# 03_PHOTOELECTRIC_SENSOR.net
KiCad netlist of a schematic drawn in Altium Designer
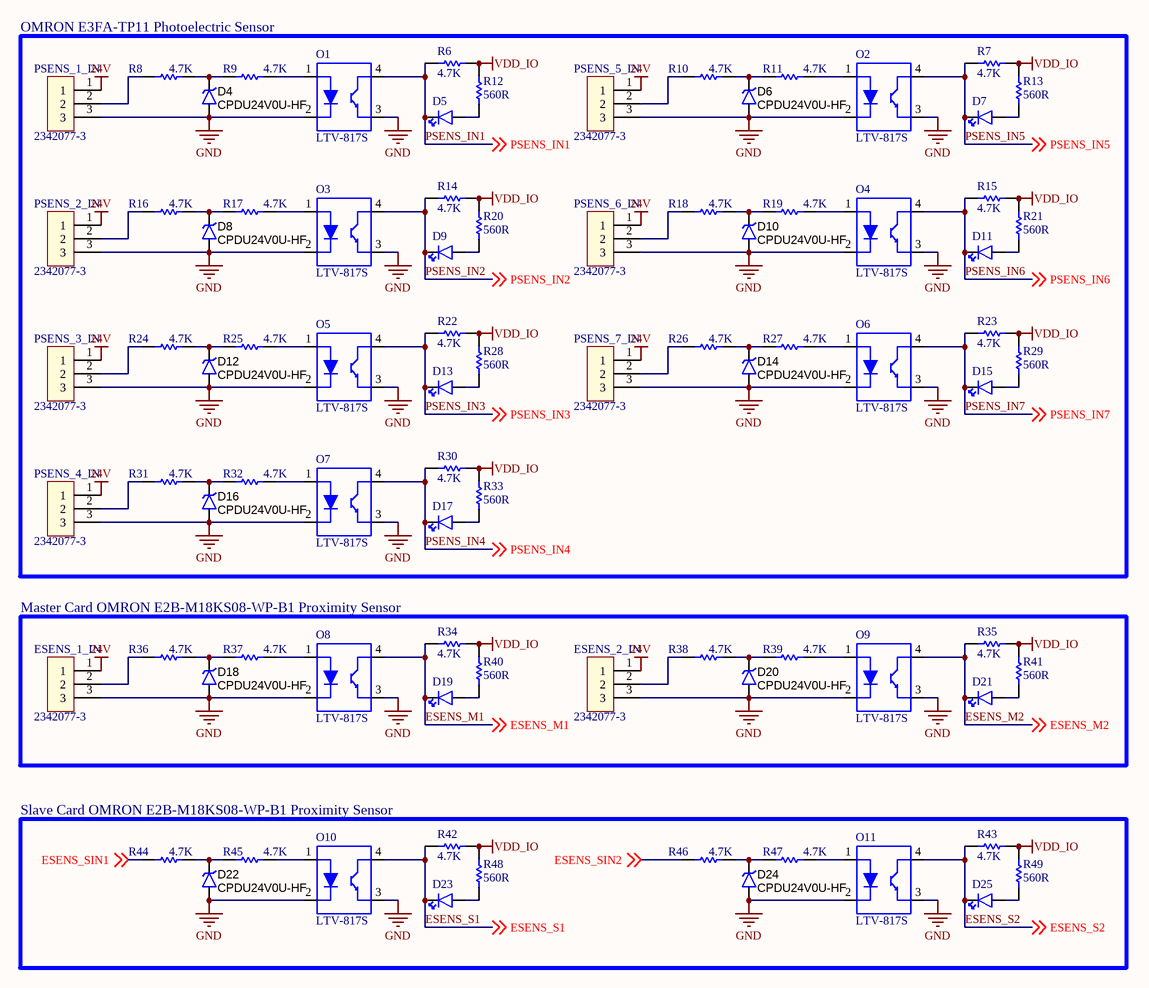
[diagram p0: 03_PHOTOELECTRIC_SENSOR.SchDoc]

(export (version "E")
  (design (tool "Eeschema 10.0.6"))
  (components
    (comp (ref "D4")
      (value "CPDU24V0U-HF")
      (footprint "SOD523F")
      (description "50V Clamp 3A (8/20µs) Ipp Tvs Diode Surface Mount 0603/SOD-523F")
      (fields
        (field (name "DIGI-KEY PART NUMBER") "641-1679-1-ND")
        (field (name "MANUFACTURER") "Comchip Technology")
      )
      (libsource (lib "FKDZ_Altium_Lib") (part "TVS DIODE 24VWM 50V 0603/SOD523F CPDU24V0U-HF"))
    )
    (comp (ref "D5")
      (value "led_green")
      (footprint "805LED")
      (description "LED 2X1.2MM 570NM GN WTR CLR SMD")
      (fields (field (name "DIGI-KEY PART NUMBER") "754-1127-1-ND"))
      (libsource (lib "FKDZ_Altium_Lib") (part "LED_GREEN_0805"))
    )
    (comp (ref "D6")
      (value "CPDU24V0U-HF")
      (footprint "SOD523F")
      (description "50V Clamp 3A (8/20µs) Ipp Tvs Diode Surface Mount 0603/SOD-523F")
      (fields
        (field (name "DIGI-KEY PART NUMBER") "641-1679-1-ND")
        (field (name "MANUFACTURER") "Comchip Technology")
      )
      (libsource (lib "FKDZ_Altium_Lib") (part "TVS DIODE 24VWM 50V 0603/SOD523F CPDU24V0U-HF"))
    )
    (comp (ref "D7")
      (value "led_green")
      (footprint "805LED")
      (description "LED 2X1.2MM 570NM GN WTR CLR SMD")
      (fields (field (name "DIGI-KEY PART NUMBER") "754-1127-1-ND"))
      (libsource (lib "FKDZ_Altium_Lib") (part "LED_GREEN_0805"))
    )
    (comp (ref "D8")
      (value "CPDU24V0U-HF")
      (footprint "SOD523F")
      (description "50V Clamp 3A (8/20µs) Ipp Tvs Diode Surface Mount 0603/SOD-523F")
      (fields
        (field (name "DIGI-KEY PART NUMBER") "641-1679-1-ND")
        (field (name "MANUFACTURER") "Comchip Technology")
      )
      (libsource (lib "FKDZ_Altium_Lib") (part "TVS DIODE 24VWM 50V 0603/SOD523F CPDU24V0U-HF"))
    )
    (comp (ref "D9")
      (value "led_green")
      (footprint "805LED")
      (description "LED 2X1.2MM 570NM GN WTR CLR SMD")
      (fields (field (name "DIGI-KEY PART NUMBER") "754-1127-1-ND"))
      (libsource (lib "FKDZ_Altium_Lib") (part "LED_GREEN_0805"))
    )
    (comp (ref "D10")
      (value "CPDU24V0U-HF")
      (footprint "SOD523F")
      (description "50V Clamp 3A (8/20µs) Ipp Tvs Diode Surface Mount 0603/SOD-523F")
      (fields
        (field (name "DIGI-KEY PART NUMBER") "641-1679-1-ND")
        (field (name "MANUFACTURER") "Comchip Technology")
      )
      (libsource (lib "FKDZ_Altium_Lib") (part "TVS DIODE 24VWM 50V 0603/SOD523F CPDU24V0U-HF"))
    )
    (comp (ref "D11")
      (value "led_green")
      (footprint "805LED")
      (description "LED 2X1.2MM 570NM GN WTR CLR SMD")
      (fields (field (name "DIGI-KEY PART NUMBER") "754-1127-1-ND"))
      (libsource (lib "FKDZ_Altium_Lib") (part "LED_GREEN_0805"))
    )
    (comp (ref "D12")
      (value "CPDU24V0U-HF")
      (footprint "SOD523F")
      (description "50V Clamp 3A (8/20µs) Ipp Tvs Diode Surface Mount 0603/SOD-523F")
      (fields
        (field (name "DIGI-KEY PART NUMBER") "641-1679-1-ND")
        (field (name "MANUFACTURER") "Comchip Technology")
      )
      (libsource (lib "FKDZ_Altium_Lib") (part "TVS DIODE 24VWM 50V 0603/SOD523F CPDU24V0U-HF"))
    )
    (comp (ref "D13")
      (value "led_green")
      (footprint "805LED")
      (description "LED 2X1.2MM 570NM GN WTR CLR SMD")
      (fields (field (name "DIGI-KEY PART NUMBER") "754-1127-1-ND"))
      (libsource (lib "FKDZ_Altium_Lib") (part "LED_GREEN_0805"))
    )
    (comp (ref "D14")
      (value "CPDU24V0U-HF")
      (footprint "SOD523F")
      (description "50V Clamp 3A (8/20µs) Ipp Tvs Diode Surface Mount 0603/SOD-523F")
      (fields
        (field (name "DIGI-KEY PART NUMBER") "641-1679-1-ND")
        (field (name "MANUFACTURER") "Comchip Technology")
      )
      (libsource (lib "FKDZ_Altium_Lib") (part "TVS DIODE 24VWM 50V 0603/SOD523F CPDU24V0U-HF"))
    )
    (comp (ref "D15")
      (value "led_green")
      (footprint "805LED")
      (description "LED 2X1.2MM 570NM GN WTR CLR SMD")
      (fields (field (name "DIGI-KEY PART NUMBER") "754-1127-1-ND"))
      (libsource (lib "FKDZ_Altium_Lib") (part "LED_GREEN_0805"))
    )
    (comp (ref "D16")
      (value "CPDU24V0U-HF")
      (footprint "SOD523F")
      (description "50V Clamp 3A (8/20µs) Ipp Tvs Diode Surface Mount 0603/SOD-523F")
      (fields
        (field (name "DIGI-KEY PART NUMBER") "641-1679-1-ND")
        (field (name "MANUFACTURER") "Comchip Technology")
      )
      (libsource (lib "FKDZ_Altium_Lib") (part "TVS DIODE 24VWM 50V 0603/SOD523F CPDU24V0U-HF"))
    )
    (comp (ref "D17")
      (value "led_green")
      (footprint "805LED")
      (description "LED 2X1.2MM 570NM GN WTR CLR SMD")
      (fields (field (name "DIGI-KEY PART NUMBER") "754-1127-1-ND"))
      (libsource (lib "FKDZ_Altium_Lib") (part "LED_GREEN_0805"))
    )
    (comp (ref "D18")
      (value "CPDU24V0U-HF")
      (footprint "SOD523F")
      (description "50V Clamp 3A (8/20µs) Ipp Tvs Diode Surface Mount 0603/SOD-523F")
      (fields
        (field (name "DIGI-KEY PART NUMBER") "641-1679-1-ND")
        (field (name "MANUFACTURER") "Comchip Technology")
      )
      (libsource (lib "FKDZ_Altium_Lib") (part "TVS DIODE 24VWM 50V 0603/SOD523F CPDU24V0U-HF"))
    )
    (comp (ref "D19")
      (value "led_green")
      (footprint "805LED")
      (description "LED 2X1.2MM 570NM GN WTR CLR SMD")
      (fields (field (name "DIGI-KEY PART NUMBER") "754-1127-1-ND"))
      (libsource (lib "FKDZ_Altium_Lib") (part "LED_GREEN_0805"))
    )
    (comp (ref "D20")
      (value "CPDU24V0U-HF")
      (footprint "SOD523F")
      (description "50V Clamp 3A (8/20µs) Ipp Tvs Diode Surface Mount 0603/SOD-523F")
      (fields
        (field (name "DIGI-KEY PART NUMBER") "641-1679-1-ND")
        (field (name "MANUFACTURER") "Comchip Technology")
      )
      (libsource (lib "FKDZ_Altium_Lib") (part "TVS DIODE 24VWM 50V 0603/SOD523F CPDU24V0U-HF"))
    )
    (comp (ref "D21")
      (value "led_green")
      (footprint "805LED")
      (description "LED 2X1.2MM 570NM GN WTR CLR SMD")
      (fields (field (name "DIGI-KEY PART NUMBER") "754-1127-1-ND"))
      (libsource (lib "FKDZ_Altium_Lib") (part "LED_GREEN_0805"))
    )
    (comp (ref "D22")
      (value "CPDU24V0U-HF")
      (footprint "SOD523F")
      (description "50V Clamp 3A (8/20µs) Ipp Tvs Diode Surface Mount 0603/SOD-523F")
      (fields
        (field (name "DIGI-KEY PART NUMBER") "641-1679-1-ND")
        (field (name "MANUFACTURER") "Comchip Technology")
      )
      (libsource (lib "FKDZ_Altium_Lib") (part "TVS DIODE 24VWM 50V 0603/SOD523F CPDU24V0U-HF"))
    )
    (comp (ref "D23")
      (value "led_green")
      (footprint "805LED")
      (description "LED 2X1.2MM 570NM GN WTR CLR SMD")
      (fields (field (name "DIGI-KEY PART NUMBER") "754-1127-1-ND"))
      (libsource (lib "FKDZ_Altium_Lib") (part "LED_GREEN_0805"))
    )
    (comp (ref "D24")
      (value "CPDU24V0U-HF")
      (footprint "SOD523F")
      (description "50V Clamp 3A (8/20µs) Ipp Tvs Diode Surface Mount 0603/SOD-523F")
      (fields
        (field (name "DIGI-KEY PART NUMBER") "641-1679-1-ND")
        (field (name "MANUFACTURER") "Comchip Technology")
      )
      (libsource (lib "FKDZ_Altium_Lib") (part "TVS DIODE 24VWM 50V 0603/SOD523F CPDU24V0U-HF"))
    )
    (comp (ref "D25")
      (value "led_green")
      (footprint "805LED")
      (description "LED 2X1.2MM 570NM GN WTR CLR SMD")
      (fields (field (name "DIGI-KEY PART NUMBER") "754-1127-1-ND"))
      (libsource (lib "FKDZ_Altium_Lib") (part "LED_GREEN_0805"))
    )
    (comp (ref "ESENS_1_IN")
      (value "2342077-3")
      (footprint "TERM BLOCK HDR 3POS 90DEG PITCH 3.81MM")
      (fields
        (field (name "DIGI-KEY PART NUMBER") "A145322-ND")
        (field (name "MANUFACTURER") "TE Connectivity AMP Connectors")
      )
      (libsource (lib "FKDZ_Altium_Lib") (part "TERM BLOCK HDR 3POS 90DEG 3.81MM"))
    )
    (comp (ref "ESENS_2_IN")
      (value "2342077-3")
      (footprint "TERM BLOCK HDR 3POS 90DEG PITCH 3.81MM")
      (fields
        (field (name "DIGI-KEY PART NUMBER") "A145322-ND")
        (field (name "MANUFACTURER") "TE Connectivity AMP Connectors")
      )
      (libsource (lib "FKDZ_Altium_Lib") (part "TERM BLOCK HDR 3POS 90DEG 3.81MM"))
    )
    (comp (ref "O1")
      (value "LTV-817S")
      (footprint "SMD4-2.54-4.6X6.5MM")
      (description "Optoisolator Transistor Output 5000Vrms 1 Channel 4-SMD")
      (fields (field (name "DIGI-KEY PART NUMBER") "160-1367-5-ND"))
      (libsource (lib "FKDZ_Altium_Lib") (part "OPTOISOLATR 5KV TRANSISTOR 4-SMD LTV-817S"))
    )
    (comp (ref "O2")
      (value "LTV-817S")
      (footprint "SMD4-2.54-4.6X6.5MM")
      (description "Optoisolator Transistor Output 5000Vrms 1 Channel 4-SMD")
      (fields (field (name "DIGI-KEY PART NUMBER") "160-1367-5-ND"))
      (libsource (lib "FKDZ_Altium_Lib") (part "OPTOISOLATR 5KV TRANSISTOR 4-SMD LTV-817S"))
    )
    (comp (ref "O3")
      (value "LTV-817S")
      (footprint "SMD4-2.54-4.6X6.5MM")
      (description "Optoisolator Transistor Output 5000Vrms 1 Channel 4-SMD")
      (fields (field (name "DIGI-KEY PART NUMBER") "160-1367-5-ND"))
      (libsource (lib "FKDZ_Altium_Lib") (part "OPTOISOLATR 5KV TRANSISTOR 4-SMD LTV-817S"))
    )
    (comp (ref "O4")
      (value "LTV-817S")
      (footprint "SMD4-2.54-4.6X6.5MM")
      (description "Optoisolator Transistor Output 5000Vrms 1 Channel 4-SMD")
      (fields (field (name "DIGI-KEY PART NUMBER") "160-1367-5-ND"))
      (libsource (lib "FKDZ_Altium_Lib") (part "OPTOISOLATR 5KV TRANSISTOR 4-SMD LTV-817S"))
    )
    (comp (ref "O5")
      (value "LTV-817S")
      (footprint "SMD4-2.54-4.6X6.5MM")
      (description "Optoisolator Transistor Output 5000Vrms 1 Channel 4-SMD")
      (fields (field (name "DIGI-KEY PART NUMBER") "160-1367-5-ND"))
      (libsource (lib "FKDZ_Altium_Lib") (part "OPTOISOLATR 5KV TRANSISTOR 4-SMD LTV-817S"))
    )
    (comp (ref "O6")
      (value "LTV-817S")
      (footprint "SMD4-2.54-4.6X6.5MM")
      (description "Optoisolator Transistor Output 5000Vrms 1 Channel 4-SMD")
      (fields (field (name "DIGI-KEY PART NUMBER") "160-1367-5-ND"))
      (libsource (lib "FKDZ_Altium_Lib") (part "OPTOISOLATR 5KV TRANSISTOR 4-SMD LTV-817S"))
    )
    (comp (ref "O7")
      (value "LTV-817S")
      (footprint "SMD4-2.54-4.6X6.5MM")
      (description "Optoisolator Transistor Output 5000Vrms 1 Channel 4-SMD")
      (fields (field (name "DIGI-KEY PART NUMBER") "160-1367-5-ND"))
      (libsource (lib "FKDZ_Altium_Lib") (part "OPTOISOLATR 5KV TRANSISTOR 4-SMD LTV-817S"))
    )
    (comp (ref "O8")
      (value "LTV-817S")
      (footprint "SMD4-2.54-4.6X6.5MM")
      (description "Optoisolator Transistor Output 5000Vrms 1 Channel 4-SMD")
      (fields (field (name "DIGI-KEY PART NUMBER") "160-1367-5-ND"))
      (libsource (lib "FKDZ_Altium_Lib") (part "OPTOISOLATR 5KV TRANSISTOR 4-SMD LTV-817S"))
    )
    (comp (ref "O9")
      (value "LTV-817S")
      (footprint "SMD4-2.54-4.6X6.5MM")
      (description "Optoisolator Transistor Output 5000Vrms 1 Channel 4-SMD")
      (fields (field (name "DIGI-KEY PART NUMBER") "160-1367-5-ND"))
      (libsource (lib "FKDZ_Altium_Lib") (part "OPTOISOLATR 5KV TRANSISTOR 4-SMD LTV-817S"))
    )
    (comp (ref "O10")
      (value "LTV-817S")
      (footprint "SMD4-2.54-4.6X6.5MM")
      (description "Optoisolator Transistor Output 5000Vrms 1 Channel 4-SMD")
      (fields (field (name "DIGI-KEY PART NUMBER") "160-1367-5-ND"))
      (libsource (lib "FKDZ_Altium_Lib") (part "OPTOISOLATR 5KV TRANSISTOR 4-SMD LTV-817S"))
    )
    (comp (ref "O11")
      (value "LTV-817S")
      (footprint "SMD4-2.54-4.6X6.5MM")
      (description "Optoisolator Transistor Output 5000Vrms 1 Channel 4-SMD")
      (fields (field (name "DIGI-KEY PART NUMBER") "160-1367-5-ND"))
      (libsource (lib "FKDZ_Altium_Lib") (part "OPTOISOLATR 5KV TRANSISTOR 4-SMD LTV-817S"))
    )
    (comp (ref "PSENS_1_IN")
      (value "2342077-3")
      (footprint "TERM BLOCK HDR 3POS 90DEG PITCH 3.81MM")
      (fields
        (field (name "DIGI-KEY PART NUMBER") "A145322-ND")
        (field (name "MANUFACTURER") "TE Connectivity AMP Connectors")
      )
      (libsource (lib "FKDZ_Altium_Lib") (part "TERM BLOCK HDR 3POS 90DEG 3.81MM"))
    )
    (comp (ref "PSENS_2_IN")
      (value "2342077-3")
      (footprint "TERM BLOCK HDR 3POS 90DEG PITCH 3.81MM")
      (fields
        (field (name "DIGI-KEY PART NUMBER") "A145322-ND")
        (field (name "MANUFACTURER") "TE Connectivity AMP Connectors")
      )
      (libsource (lib "FKDZ_Altium_Lib") (part "TERM BLOCK HDR 3POS 90DEG 3.81MM"))
    )
    (comp (ref "PSENS_3_IN")
      (value "2342077-3")
      (footprint "TERM BLOCK HDR 3POS 90DEG PITCH 3.81MM")
      (fields
        (field (name "DIGI-KEY PART NUMBER") "A145322-ND")
        (field (name "MANUFACTURER") "TE Connectivity AMP Connectors")
      )
      (libsource (lib "FKDZ_Altium_Lib") (part "TERM BLOCK HDR 3POS 90DEG 3.81MM"))
    )
    (comp (ref "PSENS_4_IN")
      (value "2342077-3")
      (footprint "TERM BLOCK HDR 3POS 90DEG PITCH 3.81MM")
      (fields
        (field (name "DIGI-KEY PART NUMBER") "A145322-ND")
        (field (name "MANUFACTURER") "TE Connectivity AMP Connectors")
      )
      (libsource (lib "FKDZ_Altium_Lib") (part "TERM BLOCK HDR 3POS 90DEG 3.81MM"))
    )
    (comp (ref "PSENS_5_IN")
      (value "2342077-3")
      (footprint "TERM BLOCK HDR 3POS 90DEG PITCH 3.81MM")
      (fields
        (field (name "DIGI-KEY PART NUMBER") "A145322-ND")
        (field (name "MANUFACTURER") "TE Connectivity AMP Connectors")
      )
      (libsource (lib "FKDZ_Altium_Lib") (part "TERM BLOCK HDR 3POS 90DEG 3.81MM"))
    )
    (comp (ref "PSENS_6_IN")
      (value "2342077-3")
      (footprint "TERM BLOCK HDR 3POS 90DEG PITCH 3.81MM")
      (fields
        (field (name "DIGI-KEY PART NUMBER") "A145322-ND")
        (field (name "MANUFACTURER") "TE Connectivity AMP Connectors")
      )
      (libsource (lib "FKDZ_Altium_Lib") (part "TERM BLOCK HDR 3POS 90DEG 3.81MM"))
    )
    (comp (ref "PSENS_7_IN")
      (value "2342077-3")
      (footprint "TERM BLOCK HDR 3POS 90DEG PITCH 3.81MM")
      (fields
        (field (name "DIGI-KEY PART NUMBER") "A145322-ND")
        (field (name "MANUFACTURER") "TE Connectivity AMP Connectors")
      )
      (libsource (lib "FKDZ_Altium_Lib") (part "TERM BLOCK HDR 3POS 90DEG 3.81MM"))
    )
    (comp (ref "R6")
      (value "4.7K")
      (footprint "603R")
      (description "4.7 kOhms ±5% 0.1W, 1/10W Chip Resistor 0603 (1608 Metric) Moisture Resistant Thick Film")
      (fields (field (name "DIGI-KEY PART NUMBER") "311-4.7KGRTR-ND") (field (name "MANUFACTURER") "Yageo"))
      (libsource (lib "FKDZ_Altium_Lib") (part "RES_4.7K_OHM_%5_0.1W_0603"))
    )
    (comp (ref "R7")
      (value "4.7K")
      (footprint "603R")
      (description "4.7 kOhms ±5% 0.1W, 1/10W Chip Resistor 0603 (1608 Metric) Moisture Resistant Thick Film")
      (fields (field (name "DIGI-KEY PART NUMBER") "311-4.7KGRTR-ND") (field (name "MANUFACTURER") "Yageo"))
      (libsource (lib "FKDZ_Altium_Lib") (part "RES_4.7K_OHM_%5_0.1W_0603"))
    )
    (comp (ref "R8")
      (value "4.7K")
      (footprint "603R")
      (description "4.7 kOhms ±5% 0.1W, 1/10W Chip Resistor 0603 (1608 Metric) Moisture Resistant Thick Film")
      (fields (field (name "DIGI-KEY PART NUMBER") "311-4.7KGRTR-ND") (field (name "MANUFACTURER") "Yageo"))
      (libsource (lib "FKDZ_Altium_Lib") (part "RES_4.7K_OHM_%5_0.1W_0603"))
    )
    (comp (ref "R9")
      (value "4.7K")
      (footprint "603R")
      (description "4.7 kOhms ±5% 0.1W, 1/10W Chip Resistor 0603 (1608 Metric) Moisture Resistant Thick Film")
      (fields (field (name "DIGI-KEY PART NUMBER") "311-4.7KGRTR-ND") (field (name "MANUFACTURER") "Yageo"))
      (libsource (lib "FKDZ_Altium_Lib") (part "RES_4.7K_OHM_%5_0.1W_0603"))
    )
    (comp (ref "R10")
      (value "4.7K")
      (footprint "603R")
      (description "4.7 kOhms ±5% 0.1W, 1/10W Chip Resistor 0603 (1608 Metric) Moisture Resistant Thick Film")
      (fields (field (name "DIGI-KEY PART NUMBER") "311-4.7KGRTR-ND") (field (name "MANUFACTURER") "Yageo"))
      (libsource (lib "FKDZ_Altium_Lib") (part "RES_4.7K_OHM_%5_0.1W_0603"))
    )
    (comp (ref "R11")
      (value "4.7K")
      (footprint "603R")
      (description "4.7 kOhms ±5% 0.1W, 1/10W Chip Resistor 0603 (1608 Metric) Moisture Resistant Thick Film")
      (fields (field (name "DIGI-KEY PART NUMBER") "311-4.7KGRTR-ND") (field (name "MANUFACTURER") "Yageo"))
      (libsource (lib "FKDZ_Altium_Lib") (part "RES_4.7K_OHM_%5_0.1W_0603"))
    )
    (comp (ref "R12")
      (value "560R")
      (footprint "603R")
      (description "560 Ohms ±5% 0.1W, 1/10W Chip Resistor 0603 (1608 Metric) Moisture Resistant Thick Film")
      (fields (field (name "DIGI-KEY PART NUMBER") "311-560GRCT-ND") (field (name "MANUFACTURER") "Yageo"))
      (libsource (lib "FKDZ_Altium_Lib") (part "RES_560_OHM_%5_0.1W_0603"))
    )
    (comp (ref "R13")
      (value "560R")
      (footprint "603R")
      (description "560 Ohms ±5% 0.1W, 1/10W Chip Resistor 0603 (1608 Metric) Moisture Resistant Thick Film")
      (fields (field (name "DIGI-KEY PART NUMBER") "311-560GRCT-ND") (field (name "MANUFACTURER") "Yageo"))
      (libsource (lib "FKDZ_Altium_Lib") (part "RES_560_OHM_%5_0.1W_0603"))
    )
    (comp (ref "R14")
      (value "4.7K")
      (footprint "603R")
      (description "4.7 kOhms ±5% 0.1W, 1/10W Chip Resistor 0603 (1608 Metric) Moisture Resistant Thick Film")
      (fields (field (name "DIGI-KEY PART NUMBER") "311-4.7KGRTR-ND") (field (name "MANUFACTURER") "Yageo"))
      (libsource (lib "FKDZ_Altium_Lib") (part "RES_4.7K_OHM_%5_0.1W_0603"))
    )
    (comp (ref "R15")
      (value "4.7K")
      (footprint "603R")
      (description "4.7 kOhms ±5% 0.1W, 1/10W Chip Resistor 0603 (1608 Metric) Moisture Resistant Thick Film")
      (fields (field (name "DIGI-KEY PART NUMBER") "311-4.7KGRTR-ND") (field (name "MANUFACTURER") "Yageo"))
      (libsource (lib "FKDZ_Altium_Lib") (part "RES_4.7K_OHM_%5_0.1W_0603"))
    )
    (comp (ref "R16")
      (value "4.7K")
      (footprint "603R")
      (description "4.7 kOhms ±5% 0.1W, 1/10W Chip Resistor 0603 (1608 Metric) Moisture Resistant Thick Film")
      (fields (field (name "DIGI-KEY PART NUMBER") "311-4.7KGRTR-ND") (field (name "MANUFACTURER") "Yageo"))
      (libsource (lib "FKDZ_Altium_Lib") (part "RES_4.7K_OHM_%5_0.1W_0603"))
    )
    (comp (ref "R17")
      (value "4.7K")
      (footprint "603R")
      (description "4.7 kOhms ±5% 0.1W, 1/10W Chip Resistor 0603 (1608 Metric) Moisture Resistant Thick Film")
      (fields (field (name "DIGI-KEY PART NUMBER") "311-4.7KGRTR-ND") (field (name "MANUFACTURER") "Yageo"))
      (libsource (lib "FKDZ_Altium_Lib") (part "RES_4.7K_OHM_%5_0.1W_0603"))
    )
    (comp (ref "R18")
      (value "4.7K")
      (footprint "603R")
      (description "4.7 kOhms ±5% 0.1W, 1/10W Chip Resistor 0603 (1608 Metric) Moisture Resistant Thick Film")
      (fields (field (name "DIGI-KEY PART NUMBER") "311-4.7KGRTR-ND") (field (name "MANUFACTURER") "Yageo"))
      (libsource (lib "FKDZ_Altium_Lib") (part "RES_4.7K_OHM_%5_0.1W_0603"))
    )
    (comp (ref "R19")
      (value "4.7K")
      (footprint "603R")
      (description "4.7 kOhms ±5% 0.1W, 1/10W Chip Resistor 0603 (1608 Metric) Moisture Resistant Thick Film")
      (fields (field (name "DIGI-KEY PART NUMBER") "311-4.7KGRTR-ND") (field (name "MANUFACTURER") "Yageo"))
      (libsource (lib "FKDZ_Altium_Lib") (part "RES_4.7K_OHM_%5_0.1W_0603"))
    )
    (comp (ref "R20")
      (value "560R")
      (footprint "603R")
      (description "560 Ohms ±5% 0.1W, 1/10W Chip Resistor 0603 (1608 Metric) Moisture Resistant Thick Film")
      (fields (field (name "DIGI-KEY PART NUMBER") "311-560GRCT-ND") (field (name "MANUFACTURER") "Yageo"))
      (libsource (lib "FKDZ_Altium_Lib") (part "RES_560_OHM_%5_0.1W_0603"))
    )
    (comp (ref "R21")
      (value "560R")
      (footprint "603R")
      (description "560 Ohms ±5% 0.1W, 1/10W Chip Resistor 0603 (1608 Metric) Moisture Resistant Thick Film")
      (fields (field (name "DIGI-KEY PART NUMBER") "311-560GRCT-ND") (field (name "MANUFACTURER") "Yageo"))
      (libsource (lib "FKDZ_Altium_Lib") (part "RES_560_OHM_%5_0.1W_0603"))
    )
    (comp (ref "R22")
      (value "4.7K")
      (footprint "603R")
      (description "4.7 kOhms ±5% 0.1W, 1/10W Chip Resistor 0603 (1608 Metric) Moisture Resistant Thick Film")
      (fields (field (name "DIGI-KEY PART NUMBER") "311-4.7KGRTR-ND") (field (name "MANUFACTURER") "Yageo"))
      (libsource (lib "FKDZ_Altium_Lib") (part "RES_4.7K_OHM_%5_0.1W_0603"))
    )
    (comp (ref "R23")
      (value "4.7K")
      (footprint "603R")
      (description "4.7 kOhms ±5% 0.1W, 1/10W Chip Resistor 0603 (1608 Metric) Moisture Resistant Thick Film")
      (fields (field (name "DIGI-KEY PART NUMBER") "311-4.7KGRTR-ND") (field (name "MANUFACTURER") "Yageo"))
      (libsource (lib "FKDZ_Altium_Lib") (part "RES_4.7K_OHM_%5_0.1W_0603"))
    )
    (comp (ref "R24")
      (value "4.7K")
      (footprint "603R")
      (description "4.7 kOhms ±5% 0.1W, 1/10W Chip Resistor 0603 (1608 Metric) Moisture Resistant Thick Film")
      (fields (field (name "DIGI-KEY PART NUMBER") "311-4.7KGRTR-ND") (field (name "MANUFACTURER") "Yageo"))
      (libsource (lib "FKDZ_Altium_Lib") (part "RES_4.7K_OHM_%5_0.1W_0603"))
    )
    (comp (ref "R25")
      (value "4.7K")
      (footprint "603R")
      (description "4.7 kOhms ±5% 0.1W, 1/10W Chip Resistor 0603 (1608 Metric) Moisture Resistant Thick Film")
      (fields (field (name "DIGI-KEY PART NUMBER") "311-4.7KGRTR-ND") (field (name "MANUFACTURER") "Yageo"))
      (libsource (lib "FKDZ_Altium_Lib") (part "RES_4.7K_OHM_%5_0.1W_0603"))
    )
    (comp (ref "R26")
      (value "4.7K")
      (footprint "603R")
      (description "4.7 kOhms ±5% 0.1W, 1/10W Chip Resistor 0603 (1608 Metric) Moisture Resistant Thick Film")
      (fields (field (name "DIGI-KEY PART NUMBER") "311-4.7KGRTR-ND") (field (name "MANUFACTURER") "Yageo"))
      (libsource (lib "FKDZ_Altium_Lib") (part "RES_4.7K_OHM_%5_0.1W_0603"))
    )
    (comp (ref "R27")
      (value "4.7K")
      (footprint "603R")
      (description "4.7 kOhms ±5% 0.1W, 1/10W Chip Resistor 0603 (1608 Metric) Moisture Resistant Thick Film")
      (fields (field (name "DIGI-KEY PART NUMBER") "311-4.7KGRTR-ND") (field (name "MANUFACTURER") "Yageo"))
      (libsource (lib "FKDZ_Altium_Lib") (part "RES_4.7K_OHM_%5_0.1W_0603"))
    )
    (comp (ref "R28")
      (value "560R")
      (footprint "603R")
      (description "560 Ohms ±5% 0.1W, 1/10W Chip Resistor 0603 (1608 Metric) Moisture Resistant Thick Film")
      (fields (field (name "DIGI-KEY PART NUMBER") "311-560GRCT-ND") (field (name "MANUFACTURER") "Yageo"))
      (libsource (lib "FKDZ_Altium_Lib") (part "RES_560_OHM_%5_0.1W_0603"))
    )
    (comp (ref "R29")
      (value "560R")
      (footprint "603R")
      (description "560 Ohms ±5% 0.1W, 1/10W Chip Resistor 0603 (1608 Metric) Moisture Resistant Thick Film")
      (fields (field (name "DIGI-KEY PART NUMBER") "311-560GRCT-ND") (field (name "MANUFACTURER") "Yageo"))
      (libsource (lib "FKDZ_Altium_Lib") (part "RES_560_OHM_%5_0.1W_0603"))
    )
    (comp (ref "R30")
      (value "4.7K")
      (footprint "603R")
      (description "4.7 kOhms ±5% 0.1W, 1/10W Chip Resistor 0603 (1608 Metric) Moisture Resistant Thick Film")
      (fields (field (name "DIGI-KEY PART NUMBER") "311-4.7KGRTR-ND") (field (name "MANUFACTURER") "Yageo"))
      (libsource (lib "FKDZ_Altium_Lib") (part "RES_4.7K_OHM_%5_0.1W_0603"))
    )
    (comp (ref "R31")
      (value "4.7K")
      (footprint "603R")
      (description "4.7 kOhms ±5% 0.1W, 1/10W Chip Resistor 0603 (1608 Metric) Moisture Resistant Thick Film")
      (fields (field (name "DIGI-KEY PART NUMBER") "311-4.7KGRTR-ND") (field (name "MANUFACTURER") "Yageo"))
      (libsource (lib "FKDZ_Altium_Lib") (part "RES_4.7K_OHM_%5_0.1W_0603"))
    )
    (comp (ref "R32")
      (value "4.7K")
      (footprint "603R")
      (description "4.7 kOhms ±5% 0.1W, 1/10W Chip Resistor 0603 (1608 Metric) Moisture Resistant Thick Film")
      (fields (field (name "DIGI-KEY PART NUMBER") "311-4.7KGRTR-ND") (field (name "MANUFACTURER") "Yageo"))
      (libsource (lib "FKDZ_Altium_Lib") (part "RES_4.7K_OHM_%5_0.1W_0603"))
    )
    (comp (ref "R33")
      (value "560R")
      (footprint "603R")
      (description "560 Ohms ±5% 0.1W, 1/10W Chip Resistor 0603 (1608 Metric) Moisture Resistant Thick Film")
      (fields (field (name "DIGI-KEY PART NUMBER") "311-560GRCT-ND") (field (name "MANUFACTURER") "Yageo"))
      (libsource (lib "FKDZ_Altium_Lib") (part "RES_560_OHM_%5_0.1W_0603"))
    )
    (comp (ref "R34")
      (value "4.7K")
      (footprint "603R")
      (description "4.7 kOhms ±5% 0.1W, 1/10W Chip Resistor 0603 (1608 Metric) Moisture Resistant Thick Film")
      (fields (field (name "DIGI-KEY PART NUMBER") "311-4.7KGRTR-ND") (field (name "MANUFACTURER") "Yageo"))
      (libsource (lib "FKDZ_Altium_Lib") (part "RES_4.7K_OHM_%5_0.1W_0603"))
    )
    (comp (ref "R35")
      (value "4.7K")
      (footprint "603R")
      (description "4.7 kOhms ±5% 0.1W, 1/10W Chip Resistor 0603 (1608 Metric) Moisture Resistant Thick Film")
      (fields (field (name "DIGI-KEY PART NUMBER") "311-4.7KGRTR-ND") (field (name "MANUFACTURER") "Yageo"))
      (libsource (lib "FKDZ_Altium_Lib") (part "RES_4.7K_OHM_%5_0.1W_0603"))
    )
    (comp (ref "R36")
      (value "4.7K")
      (footprint "603R")
      (description "4.7 kOhms ±5% 0.1W, 1/10W Chip Resistor 0603 (1608 Metric) Moisture Resistant Thick Film")
      (fields (field (name "DIGI-KEY PART NUMBER") "311-4.7KGRTR-ND") (field (name "MANUFACTURER") "Yageo"))
      (libsource (lib "FKDZ_Altium_Lib") (part "RES_4.7K_OHM_%5_0.1W_0603"))
    )
    (comp (ref "R37")
      (value "4.7K")
      (footprint "603R")
      (description "4.7 kOhms ±5% 0.1W, 1/10W Chip Resistor 0603 (1608 Metric) Moisture Resistant Thick Film")
      (fields (field (name "DIGI-KEY PART NUMBER") "311-4.7KGRTR-ND") (field (name "MANUFACTURER") "Yageo"))
      (libsource (lib "FKDZ_Altium_Lib") (part "RES_4.7K_OHM_%5_0.1W_0603"))
    )
    (comp (ref "R38")
      (value "4.7K")
      (footprint "603R")
      (description "4.7 kOhms ±5% 0.1W, 1/10W Chip Resistor 0603 (1608 Metric) Moisture Resistant Thick Film")
      (fields (field (name "DIGI-KEY PART NUMBER") "311-4.7KGRTR-ND") (field (name "MANUFACTURER") "Yageo"))
      (libsource (lib "FKDZ_Altium_Lib") (part "RES_4.7K_OHM_%5_0.1W_0603"))
    )
    (comp (ref "R39")
      (value "4.7K")
      (footprint "603R")
      (description "4.7 kOhms ±5% 0.1W, 1/10W Chip Resistor 0603 (1608 Metric) Moisture Resistant Thick Film")
      (fields (field (name "DIGI-KEY PART NUMBER") "311-4.7KGRTR-ND") (field (name "MANUFACTURER") "Yageo"))
      (libsource (lib "FKDZ_Altium_Lib") (part "RES_4.7K_OHM_%5_0.1W_0603"))
    )
    (comp (ref "R40")
      (value "560R")
      (footprint "603R")
      (description "560 Ohms ±5% 0.1W, 1/10W Chip Resistor 0603 (1608 Metric) Moisture Resistant Thick Film")
      (fields (field (name "DIGI-KEY PART NUMBER") "311-560GRCT-ND") (field (name "MANUFACTURER") "Yageo"))
      (libsource (lib "FKDZ_Altium_Lib") (part "RES_560_OHM_%5_0.1W_0603"))
    )
    (comp (ref "R41")
      (value "560R")
      (footprint "603R")
      (description "560 Ohms ±5% 0.1W, 1/10W Chip Resistor 0603 (1608 Metric) Moisture Resistant Thick Film")
      (fields (field (name "DIGI-KEY PART NUMBER") "311-560GRCT-ND") (field (name "MANUFACTURER") "Yageo"))
      (libsource (lib "FKDZ_Altium_Lib") (part "RES_560_OHM_%5_0.1W_0603"))
    )
    (comp (ref "R42")
      (value "4.7K")
      (footprint "603R")
      (description "4.7 kOhms ±5% 0.1W, 1/10W Chip Resistor 0603 (1608 Metric) Moisture Resistant Thick Film")
      (fields (field (name "DIGI-KEY PART NUMBER") "311-4.7KGRTR-ND") (field (name "MANUFACTURER") "Yageo"))
      (libsource (lib "FKDZ_Altium_Lib") (part "RES_4.7K_OHM_%5_0.1W_0603"))
    )
    (comp (ref "R43")
      (value "4.7K")
      (footprint "603R")
      (description "4.7 kOhms ±5% 0.1W, 1/10W Chip Resistor 0603 (1608 Metric) Moisture Resistant Thick Film")
      (fields (field (name "DIGI-KEY PART NUMBER") "311-4.7KGRTR-ND") (field (name "MANUFACTURER") "Yageo"))
      (libsource (lib "FKDZ_Altium_Lib") (part "RES_4.7K_OHM_%5_0.1W_0603"))
    )
    (comp (ref "R44")
      (value "4.7K")
      (footprint "603R")
      (description "4.7 kOhms ±5% 0.1W, 1/10W Chip Resistor 0603 (1608 Metric) Moisture Resistant Thick Film")
      (fields (field (name "DIGI-KEY PART NUMBER") "311-4.7KGRTR-ND") (field (name "MANUFACTURER") "Yageo"))
      (libsource (lib "FKDZ_Altium_Lib") (part "RES_4.7K_OHM_%5_0.1W_0603"))
    )
    (comp (ref "R45")
      (value "4.7K")
      (footprint "603R")
      (description "4.7 kOhms ±5% 0.1W, 1/10W Chip Resistor 0603 (1608 Metric) Moisture Resistant Thick Film")
      (fields (field (name "DIGI-KEY PART NUMBER") "311-4.7KGRTR-ND") (field (name "MANUFACTURER") "Yageo"))
      (libsource (lib "FKDZ_Altium_Lib") (part "RES_4.7K_OHM_%5_0.1W_0603"))
    )
    (comp (ref "R46")
      (value "4.7K")
      (footprint "603R")
      (description "4.7 kOhms ±5% 0.1W, 1/10W Chip Resistor 0603 (1608 Metric) Moisture Resistant Thick Film")
      (fields (field (name "DIGI-KEY PART NUMBER") "311-4.7KGRTR-ND") (field (name "MANUFACTURER") "Yageo"))
      (libsource (lib "FKDZ_Altium_Lib") (part "RES_4.7K_OHM_%5_0.1W_0603"))
    )
    (comp (ref "R47")
      (value "4.7K")
      (footprint "603R")
      (description "4.7 kOhms ±5% 0.1W, 1/10W Chip Resistor 0603 (1608 Metric) Moisture Resistant Thick Film")
      (fields (field (name "DIGI-KEY PART NUMBER") "311-4.7KGRTR-ND") (field (name "MANUFACTURER") "Yageo"))
      (libsource (lib "FKDZ_Altium_Lib") (part "RES_4.7K_OHM_%5_0.1W_0603"))
    )
    (comp (ref "R48")
      (value "560R")
      (footprint "603R")
      (description "560 Ohms ±5% 0.1W, 1/10W Chip Resistor 0603 (1608 Metric) Moisture Resistant Thick Film")
      (fields (field (name "DIGI-KEY PART NUMBER") "311-560GRCT-ND") (field (name "MANUFACTURER") "Yageo"))
      (libsource (lib "FKDZ_Altium_Lib") (part "RES_560_OHM_%5_0.1W_0603"))
    )
    (comp (ref "R49")
      (value "560R")
      (footprint "603R")
      (description "560 Ohms ±5% 0.1W, 1/10W Chip Resistor 0603 (1608 Metric) Moisture Resistant Thick Film")
      (fields (field (name "DIGI-KEY PART NUMBER") "311-560GRCT-ND") (field (name "MANUFACTURER") "Yageo"))
      (libsource (lib "FKDZ_Altium_Lib") (part "RES_560_OHM_%5_0.1W_0603"))
    )
  )
  (nets
    (net (code "1") (name "24V") (class "Default")
      (node (ref "ESENS_1_IN") (pin "1") (pinfunction "1_1") (pintype "passive"))
      (node (ref "ESENS_2_IN") (pin "1") (pinfunction "1_1") (pintype "passive"))
      (node (ref "PSENS_1_IN") (pin "1") (pinfunction "1_1") (pintype "passive"))
      (node (ref "PSENS_2_IN") (pin "1") (pinfunction "1_1") (pintype "passive"))
      (node (ref "PSENS_3_IN") (pin "1") (pinfunction "1_1") (pintype "passive"))
      (node (ref "PSENS_4_IN") (pin "1") (pinfunction "1_1") (pintype "passive"))
      (node (ref "PSENS_5_IN") (pin "1") (pinfunction "1_1") (pintype "passive"))
      (node (ref "PSENS_6_IN") (pin "1") (pinfunction "1_1") (pintype "passive"))
      (node (ref "PSENS_7_IN") (pin "1") (pinfunction "1_1") (pintype "passive"))
    )
    (net (code "2") (name "ESENS_M1") (class "Default")
      (node (ref "D19") (pin "2") (pinfunction "K_2") (pintype "passive"))
      (node (ref "O8") (pin "4") (pinfunction "COLLECTOR_4") (pintype "passive"))
      (node (ref "R34") (pin "1") (pinfunction "1_1") (pintype "passive"))
    )
    (net (code "3") (name "ESENS_M2") (class "Default")
      (node (ref "D21") (pin "2") (pinfunction "K_2") (pintype "passive"))
      (node (ref "O9") (pin "4") (pinfunction "COLLECTOR_4") (pintype "passive"))
      (node (ref "R35") (pin "1") (pinfunction "1_1") (pintype "passive"))
    )
    (net (code "4") (name "ESENS_S1") (class "Default")
      (node (ref "D23") (pin "2") (pinfunction "K_2") (pintype "passive"))
      (node (ref "O10") (pin "4") (pinfunction "COLLECTOR_4") (pintype "passive"))
      (node (ref "R42") (pin "1") (pinfunction "1_1") (pintype "passive"))
    )
    (net (code "5") (name "ESENS_S2") (class "Default")
      (node (ref "D25") (pin "2") (pinfunction "K_2") (pintype "passive"))
      (node (ref "O11") (pin "4") (pinfunction "COLLECTOR_4") (pintype "passive"))
      (node (ref "R43") (pin "1") (pinfunction "1_1") (pintype "passive"))
    )
    (net (code "6") (name "ESENS_SIN1") (class "Default")
      (node (ref "R44") (pin "1") (pinfunction "1_1") (pintype "passive"))
    )
    (net (code "7") (name "ESENS_SIN2") (class "Default")
      (node (ref "R46") (pin "1") (pinfunction "1_1") (pintype "passive"))
    )
    (net (code "8") (name "GND") (class "Default")
      (node (ref "D10") (pin "1") (pinfunction "1_1") (pintype "passive"))
      (node (ref "D12") (pin "1") (pinfunction "1_1") (pintype "passive"))
      (node (ref "D14") (pin "1") (pinfunction "1_1") (pintype "passive"))
      (node (ref "D16") (pin "1") (pinfunction "1_1") (pintype "passive"))
      (node (ref "D18") (pin "1") (pinfunction "1_1") (pintype "passive"))
      (node (ref "D20") (pin "1") (pinfunction "1_1") (pintype "passive"))
      (node (ref "D22") (pin "1") (pinfunction "1_1") (pintype "passive"))
      (node (ref "D24") (pin "1") (pinfunction "1_1") (pintype "passive"))
      (node (ref "D4") (pin "1") (pinfunction "1_1") (pintype "passive"))
      (node (ref "D6") (pin "1") (pinfunction "1_1") (pintype "passive"))
      (node (ref "D8") (pin "1") (pinfunction "1_1") (pintype "passive"))
      (node (ref "ESENS_1_IN") (pin "3") (pinfunction "3_3") (pintype "passive"))
      (node (ref "ESENS_2_IN") (pin "3") (pinfunction "3_3") (pintype "passive"))
      (node (ref "O1") (pin "2") (pinfunction "CATHODE_2") (pintype "passive"))
      (node (ref "O1") (pin "3") (pinfunction "EMITER_3") (pintype "passive"))
      (node (ref "O10") (pin "2") (pinfunction "CATHODE_2") (pintype "passive"))
      (node (ref "O10") (pin "3") (pinfunction "EMITER_3") (pintype "passive"))
      (node (ref "O11") (pin "2") (pinfunction "CATHODE_2") (pintype "passive"))
      (node (ref "O11") (pin "3") (pinfunction "EMITER_3") (pintype "passive"))
      (node (ref "O2") (pin "2") (pinfunction "CATHODE_2") (pintype "passive"))
      (node (ref "O2") (pin "3") (pinfunction "EMITER_3") (pintype "passive"))
      (node (ref "O3") (pin "2") (pinfunction "CATHODE_2") (pintype "passive"))
      (node (ref "O3") (pin "3") (pinfunction "EMITER_3") (pintype "passive"))
      (node (ref "O4") (pin "2") (pinfunction "CATHODE_2") (pintype "passive"))
      (node (ref "O4") (pin "3") (pinfunction "EMITER_3") (pintype "passive"))
      (node (ref "O5") (pin "2") (pinfunction "CATHODE_2") (pintype "passive"))
      (node (ref "O5") (pin "3") (pinfunction "EMITER_3") (pintype "passive"))
      (node (ref "O6") (pin "2") (pinfunction "CATHODE_2") (pintype "passive"))
      (node (ref "O6") (pin "3") (pinfunction "EMITER_3") (pintype "passive"))
      (node (ref "O7") (pin "2") (pinfunction "CATHODE_2") (pintype "passive"))
      (node (ref "O7") (pin "3") (pinfunction "EMITER_3") (pintype "passive"))
      (node (ref "O8") (pin "2") (pinfunction "CATHODE_2") (pintype "passive"))
      (node (ref "O8") (pin "3") (pinfunction "EMITER_3") (pintype "passive"))
      (node (ref "O9") (pin "2") (pinfunction "CATHODE_2") (pintype "passive"))
      (node (ref "O9") (pin "3") (pinfunction "EMITER_3") (pintype "passive"))
      (node (ref "PSENS_1_IN") (pin "3") (pinfunction "3_3") (pintype "passive"))
      (node (ref "PSENS_2_IN") (pin "3") (pinfunction "3_3") (pintype "passive"))
      (node (ref "PSENS_3_IN") (pin "3") (pinfunction "3_3") (pintype "passive"))
      (node (ref "PSENS_4_IN") (pin "3") (pinfunction "3_3") (pintype "passive"))
      (node (ref "PSENS_5_IN") (pin "3") (pinfunction "3_3") (pintype "passive"))
      (node (ref "PSENS_6_IN") (pin "3") (pinfunction "3_3") (pintype "passive"))
      (node (ref "PSENS_7_IN") (pin "3") (pinfunction "3_3") (pintype "passive"))
    )
    (net (code "9") (name "Net-(D4-Pad2)") (class "Default")
      (node (ref "D4") (pin "2") (pinfunction "2_2") (pintype "passive"))
      (node (ref "R8") (pin "2") (pinfunction "2_2") (pintype "passive"))
      (node (ref "R9") (pin "1") (pinfunction "1_1") (pintype "passive"))
    )
    (net (code "10") (name "Net-(D5-A)") (class "Default")
      (node (ref "D5") (pin "1") (pinfunction "A_1") (pintype "passive"))
      (node (ref "R12") (pin "1") (pinfunction "1_1") (pintype "passive"))
    )
    (net (code "11") (name "Net-(D6-Pad2)") (class "Default")
      (node (ref "D6") (pin "2") (pinfunction "2_2") (pintype "passive"))
      (node (ref "R10") (pin "2") (pinfunction "2_2") (pintype "passive"))
      (node (ref "R11") (pin "1") (pinfunction "1_1") (pintype "passive"))
    )
    (net (code "12") (name "Net-(D7-A)") (class "Default")
      (node (ref "D7") (pin "1") (pinfunction "A_1") (pintype "passive"))
      (node (ref "R13") (pin "1") (pinfunction "1_1") (pintype "passive"))
    )
    (net (code "13") (name "Net-(D8-Pad2)") (class "Default")
      (node (ref "D8") (pin "2") (pinfunction "2_2") (pintype "passive"))
      (node (ref "R16") (pin "2") (pinfunction "2_2") (pintype "passive"))
      (node (ref "R17") (pin "1") (pinfunction "1_1") (pintype "passive"))
    )
    (net (code "14") (name "Net-(D9-A)") (class "Default")
      (node (ref "D9") (pin "1") (pinfunction "A_1") (pintype "passive"))
      (node (ref "R20") (pin "1") (pinfunction "1_1") (pintype "passive"))
    )
    (net (code "15") (name "Net-(D10-Pad2)") (class "Default")
      (node (ref "D10") (pin "2") (pinfunction "2_2") (pintype "passive"))
      (node (ref "R18") (pin "2") (pinfunction "2_2") (pintype "passive"))
      (node (ref "R19") (pin "1") (pinfunction "1_1") (pintype "passive"))
    )
    (net (code "16") (name "Net-(D11-A)") (class "Default")
      (node (ref "D11") (pin "1") (pinfunction "A_1") (pintype "passive"))
      (node (ref "R21") (pin "1") (pinfunction "1_1") (pintype "passive"))
    )
    (net (code "17") (name "Net-(D12-Pad2)") (class "Default")
      (node (ref "D12") (pin "2") (pinfunction "2_2") (pintype "passive"))
      (node (ref "R24") (pin "2") (pinfunction "2_2") (pintype "passive"))
      (node (ref "R25") (pin "1") (pinfunction "1_1") (pintype "passive"))
    )
    (net (code "18") (name "Net-(D13-A)") (class "Default")
      (node (ref "D13") (pin "1") (pinfunction "A_1") (pintype "passive"))
      (node (ref "R28") (pin "1") (pinfunction "1_1") (pintype "passive"))
    )
    (net (code "19") (name "Net-(D14-Pad2)") (class "Default")
      (node (ref "D14") (pin "2") (pinfunction "2_2") (pintype "passive"))
      (node (ref "R26") (pin "2") (pinfunction "2_2") (pintype "passive"))
      (node (ref "R27") (pin "1") (pinfunction "1_1") (pintype "passive"))
    )
    (net (code "20") (name "Net-(D15-A)") (class "Default")
      (node (ref "D15") (pin "1") (pinfunction "A_1") (pintype "passive"))
      (node (ref "R29") (pin "1") (pinfunction "1_1") (pintype "passive"))
    )
    (net (code "21") (name "Net-(D16-Pad2)") (class "Default")
      (node (ref "D16") (pin "2") (pinfunction "2_2") (pintype "passive"))
      (node (ref "R31") (pin "2") (pinfunction "2_2") (pintype "passive"))
      (node (ref "R32") (pin "1") (pinfunction "1_1") (pintype "passive"))
    )
    (net (code "22") (name "Net-(D17-A)") (class "Default")
      (node (ref "D17") (pin "1") (pinfunction "A_1") (pintype "passive"))
      (node (ref "R33") (pin "1") (pinfunction "1_1") (pintype "passive"))
    )
    (net (code "23") (name "Net-(D18-Pad2)") (class "Default")
      (node (ref "D18") (pin "2") (pinfunction "2_2") (pintype "passive"))
      (node (ref "R36") (pin "2") (pinfunction "2_2") (pintype "passive"))
      (node (ref "R37") (pin "1") (pinfunction "1_1") (pintype "passive"))
    )
    (net (code "24") (name "Net-(D19-A)") (class "Default")
      (node (ref "D19") (pin "1") (pinfunction "A_1") (pintype "passive"))
      (node (ref "R40") (pin "1") (pinfunction "1_1") (pintype "passive"))
    )
    (net (code "25") (name "Net-(D20-Pad2)") (class "Default")
      (node (ref "D20") (pin "2") (pinfunction "2_2") (pintype "passive"))
      (node (ref "R38") (pin "2") (pinfunction "2_2") (pintype "passive"))
      (node (ref "R39") (pin "1") (pinfunction "1_1") (pintype "passive"))
    )
    (net (code "26") (name "Net-(D21-A)") (class "Default")
      (node (ref "D21") (pin "1") (pinfunction "A_1") (pintype "passive"))
      (node (ref "R41") (pin "1") (pinfunction "1_1") (pintype "passive"))
    )
    (net (code "27") (name "Net-(D22-Pad2)") (class "Default")
      (node (ref "D22") (pin "2") (pinfunction "2_2") (pintype "passive"))
      (node (ref "R44") (pin "2") (pinfunction "2_2") (pintype "passive"))
      (node (ref "R45") (pin "1") (pinfunction "1_1") (pintype "passive"))
    )
    (net (code "28") (name "Net-(D23-A)") (class "Default")
      (node (ref "D23") (pin "1") (pinfunction "A_1") (pintype "passive"))
      (node (ref "R48") (pin "1") (pinfunction "1_1") (pintype "passive"))
    )
    (net (code "29") (name "Net-(D24-Pad2)") (class "Default")
      (node (ref "D24") (pin "2") (pinfunction "2_2") (pintype "passive"))
      (node (ref "R46") (pin "2") (pinfunction "2_2") (pintype "passive"))
      (node (ref "R47") (pin "1") (pinfunction "1_1") (pintype "passive"))
    )
    (net (code "30") (name "Net-(D25-A)") (class "Default")
      (node (ref "D25") (pin "1") (pinfunction "A_1") (pintype "passive"))
      (node (ref "R49") (pin "1") (pinfunction "1_1") (pintype "passive"))
    )
    (net (code "31") (name "Net-(ESENS_1_IN-Pad2)") (class "Default")
      (node (ref "ESENS_1_IN") (pin "2") (pinfunction "2_2") (pintype "passive"))
      (node (ref "R36") (pin "1") (pinfunction "1_1") (pintype "passive"))
    )
    (net (code "32") (name "Net-(ESENS_2_IN-Pad2)") (class "Default")
      (node (ref "ESENS_2_IN") (pin "2") (pinfunction "2_2") (pintype "passive"))
      (node (ref "R38") (pin "1") (pinfunction "1_1") (pintype "passive"))
    )
    (net (code "33") (name "Net-(O1-ANODE)") (class "Default")
      (node (ref "O1") (pin "1") (pinfunction "ANODE_1") (pintype "passive"))
      (node (ref "R9") (pin "2") (pinfunction "2_2") (pintype "passive"))
    )
    (net (code "34") (name "Net-(O2-ANODE)") (class "Default")
      (node (ref "O2") (pin "1") (pinfunction "ANODE_1") (pintype "passive"))
      (node (ref "R11") (pin "2") (pinfunction "2_2") (pintype "passive"))
    )
    (net (code "35") (name "Net-(O3-ANODE)") (class "Default")
      (node (ref "O3") (pin "1") (pinfunction "ANODE_1") (pintype "passive"))
      (node (ref "R17") (pin "2") (pinfunction "2_2") (pintype "passive"))
    )
    (net (code "36") (name "Net-(O4-ANODE)") (class "Default")
      (node (ref "O4") (pin "1") (pinfunction "ANODE_1") (pintype "passive"))
      (node (ref "R19") (pin "2") (pinfunction "2_2") (pintype "passive"))
    )
    (net (code "37") (name "Net-(O5-ANODE)") (class "Default")
      (node (ref "O5") (pin "1") (pinfunction "ANODE_1") (pintype "passive"))
      (node (ref "R25") (pin "2") (pinfunction "2_2") (pintype "passive"))
    )
    (net (code "38") (name "Net-(O6-ANODE)") (class "Default")
      (node (ref "O6") (pin "1") (pinfunction "ANODE_1") (pintype "passive"))
      (node (ref "R27") (pin "2") (pinfunction "2_2") (pintype "passive"))
    )
    (net (code "39") (name "Net-(O7-ANODE)") (class "Default")
      (node (ref "O7") (pin "1") (pinfunction "ANODE_1") (pintype "passive"))
      (node (ref "R32") (pin "2") (pinfunction "2_2") (pintype "passive"))
    )
    (net (code "40") (name "Net-(O8-ANODE)") (class "Default")
      (node (ref "O8") (pin "1") (pinfunction "ANODE_1") (pintype "passive"))
      (node (ref "R37") (pin "2") (pinfunction "2_2") (pintype "passive"))
    )
    (net (code "41") (name "Net-(O9-ANODE)") (class "Default")
      (node (ref "O9") (pin "1") (pinfunction "ANODE_1") (pintype "passive"))
      (node (ref "R39") (pin "2") (pinfunction "2_2") (pintype "passive"))
    )
    (net (code "42") (name "Net-(O10-ANODE)") (class "Default")
      (node (ref "O10") (pin "1") (pinfunction "ANODE_1") (pintype "passive"))
      (node (ref "R45") (pin "2") (pinfunction "2_2") (pintype "passive"))
    )
    (net (code "43") (name "Net-(O11-ANODE)") (class "Default")
      (node (ref "O11") (pin "1") (pinfunction "ANODE_1") (pintype "passive"))
      (node (ref "R47") (pin "2") (pinfunction "2_2") (pintype "passive"))
    )
    (net (code "44") (name "Net-(PSENS_1_IN-Pad2)") (class "Default")
      (node (ref "PSENS_1_IN") (pin "2") (pinfunction "2_2") (pintype "passive"))
      (node (ref "R8") (pin "1") (pinfunction "1_1") (pintype "passive"))
    )
    (net (code "45") (name "Net-(PSENS_2_IN-Pad2)") (class "Default")
      (node (ref "PSENS_2_IN") (pin "2") (pinfunction "2_2") (pintype "passive"))
      (node (ref "R16") (pin "1") (pinfunction "1_1") (pintype "passive"))
    )
    (net (code "46") (name "Net-(PSENS_3_IN-Pad2)") (class "Default")
      (node (ref "PSENS_3_IN") (pin "2") (pinfunction "2_2") (pintype "passive"))
      (node (ref "R24") (pin "1") (pinfunction "1_1") (pintype "passive"))
    )
    (net (code "47") (name "Net-(PSENS_4_IN-Pad2)") (class "Default")
      (node (ref "PSENS_4_IN") (pin "2") (pinfunction "2_2") (pintype "passive"))
      (node (ref "R31") (pin "1") (pinfunction "1_1") (pintype "passive"))
    )
    (net (code "48") (name "Net-(PSENS_5_IN-Pad2)") (class "Default")
      (node (ref "PSENS_5_IN") (pin "2") (pinfunction "2_2") (pintype "passive"))
      (node (ref "R10") (pin "1") (pinfunction "1_1") (pintype "passive"))
    )
    (net (code "49") (name "Net-(PSENS_6_IN-Pad2)") (class "Default")
      (node (ref "PSENS_6_IN") (pin "2") (pinfunction "2_2") (pintype "passive"))
      (node (ref "R18") (pin "1") (pinfunction "1_1") (pintype "passive"))
    )
    (net (code "50") (name "Net-(PSENS_7_IN-Pad2)") (class "Default")
      (node (ref "PSENS_7_IN") (pin "2") (pinfunction "2_2") (pintype "passive"))
      (node (ref "R26") (pin "1") (pinfunction "1_1") (pintype "passive"))
    )
    (net (code "51") (name "PSENS_IN1") (class "Default")
      (node (ref "D5") (pin "2") (pinfunction "K_2") (pintype "passive"))
      (node (ref "O1") (pin "4") (pinfunction "COLLECTOR_4") (pintype "passive"))
      (node (ref "R6") (pin "1") (pinfunction "1_1") (pintype "passive"))
    )
    (net (code "52") (name "PSENS_IN2") (class "Default")
      (node (ref "D9") (pin "2") (pinfunction "K_2") (pintype "passive"))
      (node (ref "O3") (pin "4") (pinfunction "COLLECTOR_4") (pintype "passive"))
      (node (ref "R14") (pin "1") (pinfunction "1_1") (pintype "passive"))
    )
    (net (code "53") (name "PSENS_IN3") (class "Default")
      (node (ref "D13") (pin "2") (pinfunction "K_2") (pintype "passive"))
      (node (ref "O5") (pin "4") (pinfunction "COLLECTOR_4") (pintype "passive"))
      (node (ref "R22") (pin "1") (pinfunction "1_1") (pintype "passive"))
    )
    (net (code "54") (name "PSENS_IN4") (class "Default")
      (node (ref "D17") (pin "2") (pinfunction "K_2") (pintype "passive"))
      (node (ref "O7") (pin "4") (pinfunction "COLLECTOR_4") (pintype "passive"))
      (node (ref "R30") (pin "1") (pinfunction "1_1") (pintype "passive"))
    )
    (net (code "55") (name "PSENS_IN5") (class "Default")
      (node (ref "D7") (pin "2") (pinfunction "K_2") (pintype "passive"))
      (node (ref "O2") (pin "4") (pinfunction "COLLECTOR_4") (pintype "passive"))
      (node (ref "R7") (pin "1") (pinfunction "1_1") (pintype "passive"))
    )
    (net (code "56") (name "PSENS_IN6") (class "Default")
      (node (ref "D11") (pin "2") (pinfunction "K_2") (pintype "passive"))
      (node (ref "O4") (pin "4") (pinfunction "COLLECTOR_4") (pintype "passive"))
      (node (ref "R15") (pin "1") (pinfunction "1_1") (pintype "passive"))
    )
    (net (code "57") (name "PSENS_IN7") (class "Default")
      (node (ref "D15") (pin "2") (pinfunction "K_2") (pintype "passive"))
      (node (ref "O6") (pin "4") (pinfunction "COLLECTOR_4") (pintype "passive"))
      (node (ref "R23") (pin "1") (pinfunction "1_1") (pintype "passive"))
    )
    (net (code "58") (name "VDD_IO") (class "Default")
      (node (ref "R12") (pin "2") (pinfunction "2_2") (pintype "passive"))
      (node (ref "R13") (pin "2") (pinfunction "2_2") (pintype "passive"))
      (node (ref "R14") (pin "2") (pinfunction "2_2") (pintype "passive"))
      (node (ref "R15") (pin "2") (pinfunction "2_2") (pintype "passive"))
      (node (ref "R20") (pin "2") (pinfunction "2_2") (pintype "passive"))
      (node (ref "R21") (pin "2") (pinfunction "2_2") (pintype "passive"))
      (node (ref "R22") (pin "2") (pinfunction "2_2") (pintype "passive"))
      (node (ref "R23") (pin "2") (pinfunction "2_2") (pintype "passive"))
      (node (ref "R28") (pin "2") (pinfunction "2_2") (pintype "passive"))
      (node (ref "R29") (pin "2") (pinfunction "2_2") (pintype "passive"))
      (node (ref "R30") (pin "2") (pinfunction "2_2") (pintype "passive"))
      (node (ref "R33") (pin "2") (pinfunction "2_2") (pintype "passive"))
      (node (ref "R34") (pin "2") (pinfunction "2_2") (pintype "passive"))
      (node (ref "R35") (pin "2") (pinfunction "2_2") (pintype "passive"))
      (node (ref "R40") (pin "2") (pinfunction "2_2") (pintype "passive"))
      (node (ref "R41") (pin "2") (pinfunction "2_2") (pintype "passive"))
      (node (ref "R42") (pin "2") (pinfunction "2_2") (pintype "passive"))
      (node (ref "R43") (pin "2") (pinfunction "2_2") (pintype "passive"))
      (node (ref "R48") (pin "2") (pinfunction "2_2") (pintype "passive"))
      (node (ref "R49") (pin "2") (pinfunction "2_2") (pintype "passive"))
      (node (ref "R6") (pin "2") (pinfunction "2_2") (pintype "passive"))
      (node (ref "R7") (pin "2") (pinfunction "2_2") (pintype "passive"))
    )
  )
)
